# DeMuxRow.net
KiCad netlist of a schematic drawn in EAGLE
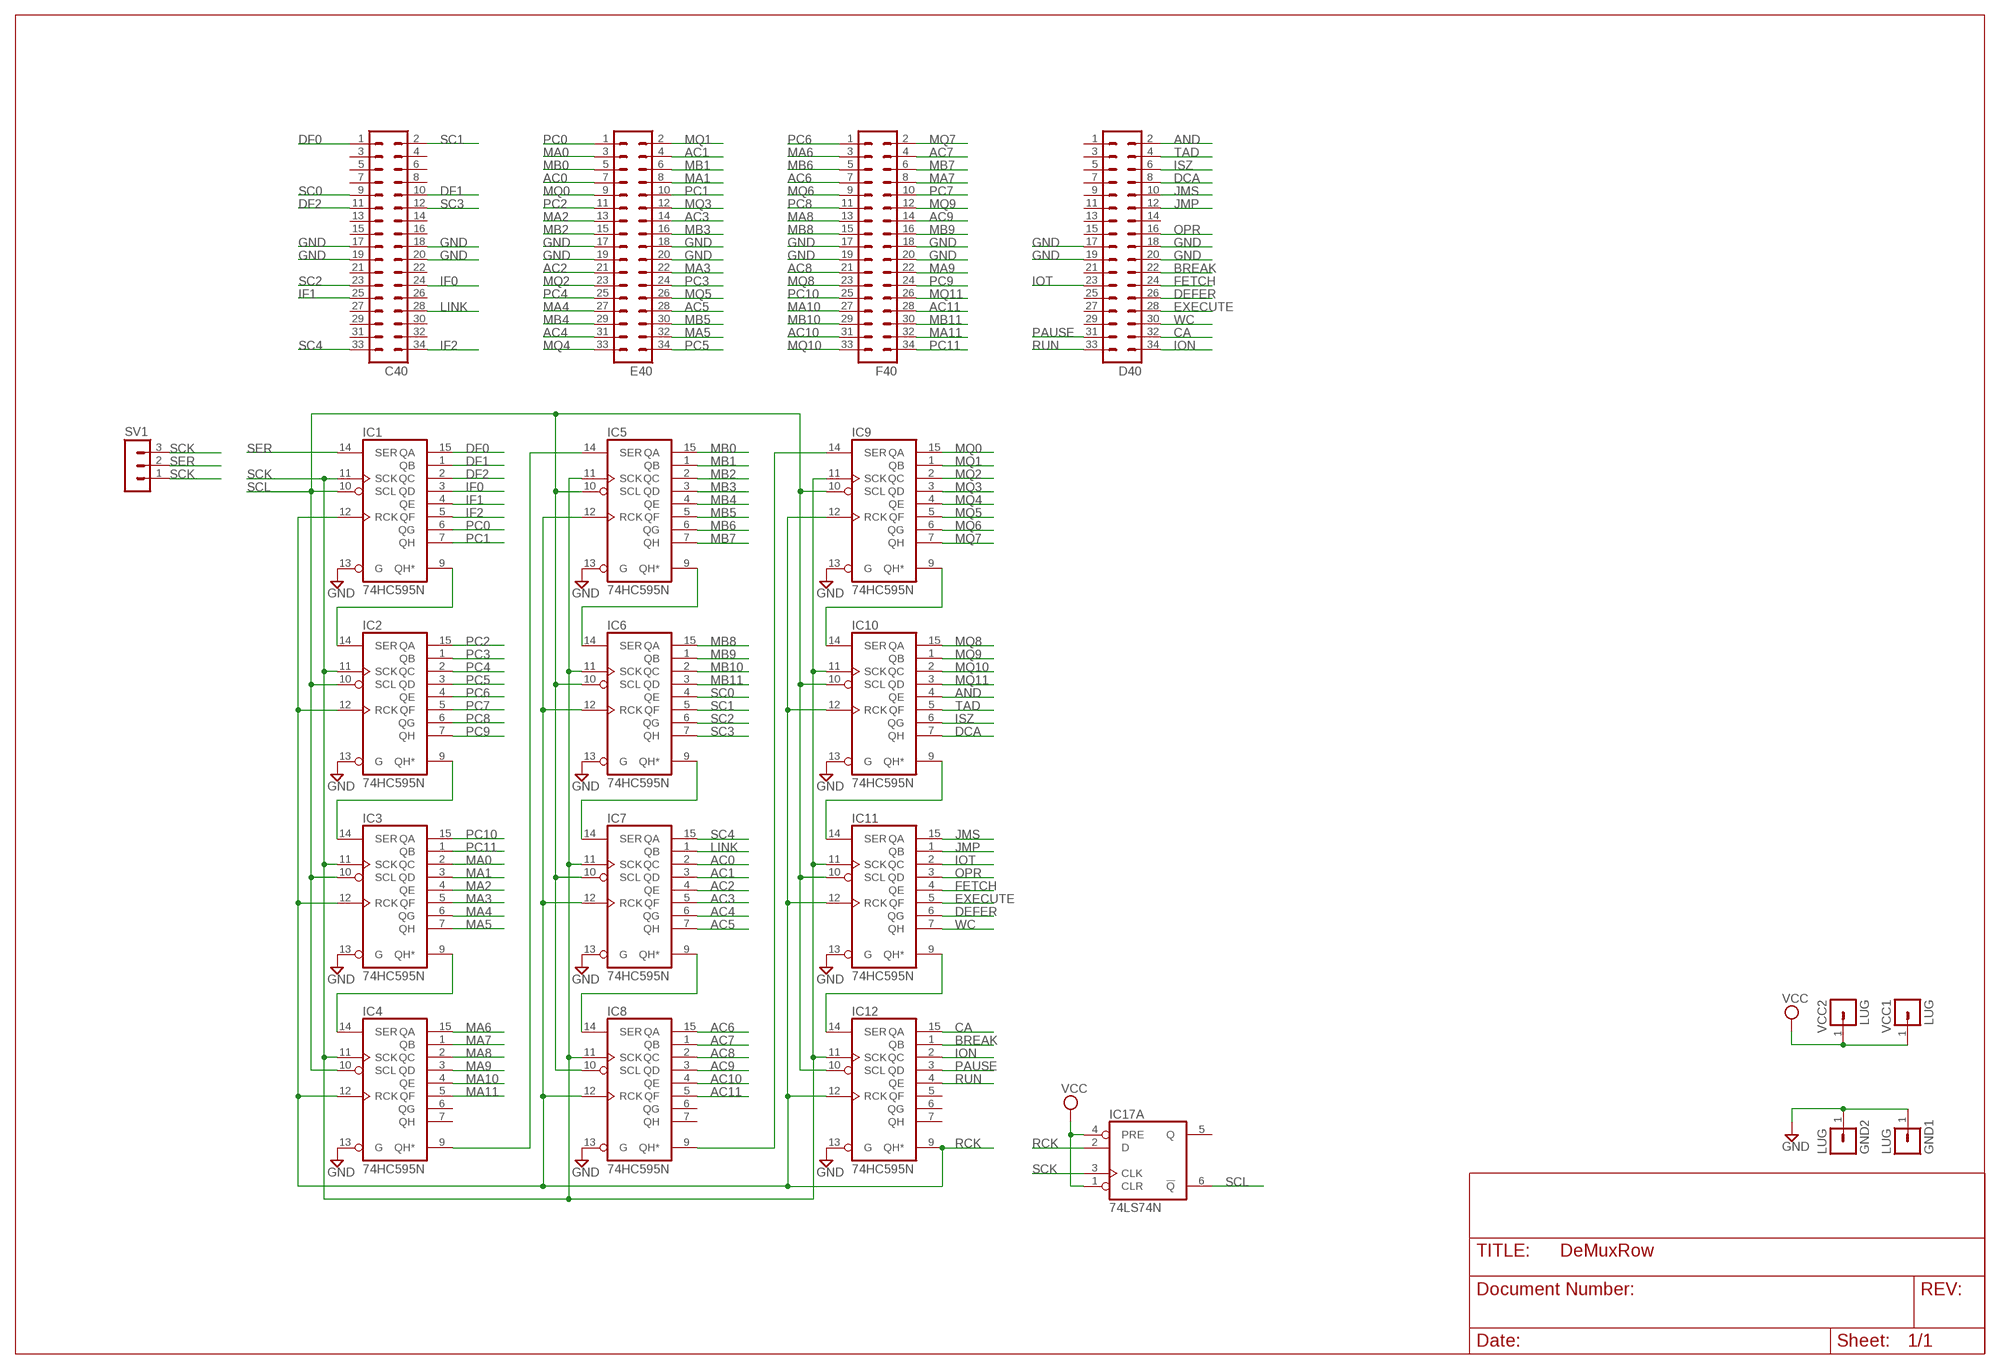
[diagram p0: schematic, sheet 1]

(export (version "E")
  (design (tool "Eeschema 10.0.6"))
  (components
    (comp (ref "C40")
      (value "MA17-2")
      (footprint "eagle-import:MA17-2")
      (libsource (lib "eagle-import") (part "MA17-2"))
    )
    (comp (ref "D40")
      (value "MA17-2")
      (footprint "eagle-import:MA17-2")
      (libsource (lib "eagle-import") (part "MA17-2"))
    )
    (comp (ref "E40")
      (value "MA17-2")
      (footprint "eagle-import:MA17-2")
      (libsource (lib "eagle-import") (part "MA17-2"))
    )
    (comp (ref "F40")
      (value "MA17-2")
      (footprint "eagle-import:MA17-2")
      (libsource (lib "eagle-import") (part "MA17-2"))
    )
    (comp (ref "GND1")
      (value "LUG")
      (footprint "eagle-import:SPADELUG")
      (libsource (lib "eagle-import") (part "LUG"))
    )
    (comp (ref "GND2")
      (value "LUG")
      (footprint "eagle-import:SPADELUG")
      (libsource (lib "eagle-import") (part "LUG"))
    )
    (comp (ref "IC1")
      (value "74HC595N")
      (footprint "eagle-import:DIL16")
      (libsource (lib "eagle-import") (part "74595NLS"))
    )
    (comp (ref "IC2")
      (value "74HC595N")
      (footprint "eagle-import:DIL16")
      (libsource (lib "eagle-import") (part "74595NLS"))
    )
    (comp (ref "IC3")
      (value "74HC595N")
      (footprint "eagle-import:DIL16")
      (libsource (lib "eagle-import") (part "74595NLS"))
    )
    (comp (ref "IC4")
      (value "74HC595N")
      (footprint "eagle-import:DIL16")
      (libsource (lib "eagle-import") (part "74595NLS"))
    )
    (comp (ref "IC5")
      (value "74HC595N")
      (footprint "eagle-import:DIL16")
      (libsource (lib "eagle-import") (part "74595NLS"))
    )
    (comp (ref "IC6")
      (value "74HC595N")
      (footprint "eagle-import:DIL16")
      (libsource (lib "eagle-import") (part "74595NLS"))
    )
    (comp (ref "IC7")
      (value "74HC595N")
      (footprint "eagle-import:DIL16")
      (libsource (lib "eagle-import") (part "74595NLS"))
    )
    (comp (ref "IC8")
      (value "74HC595N")
      (footprint "eagle-import:DIL16")
      (libsource (lib "eagle-import") (part "74595NLS"))
    )
    (comp (ref "IC9")
      (value "74HC595N")
      (footprint "eagle-import:DIL16")
      (libsource (lib "eagle-import") (part "74595NLS"))
    )
    (comp (ref "IC10")
      (value "74HC595N")
      (footprint "eagle-import:DIL16")
      (libsource (lib "eagle-import") (part "74595NLS"))
    )
    (comp (ref "IC11")
      (value "74HC595N")
      (footprint "eagle-import:DIL16")
      (libsource (lib "eagle-import") (part "74595NLS"))
    )
    (comp (ref "IC12")
      (value "74HC595N")
      (footprint "eagle-import:DIL16")
      (libsource (lib "eagle-import") (part "74595NLS"))
    )
    (comp (ref "IC17")
      (value "74LS74N")
      (footprint "eagle-import:DIL14")
      (libsource (lib "eagle-import") (part "7474NLS"))
    )
    (comp (ref "SV1")
      (value "MA03-1")
      (footprint "eagle-import:MA03-1")
      (libsource (lib "eagle-import") (part "MA03-1"))
    )
    (comp (ref "VCC1")
      (value "LUG")
      (footprint "eagle-import:SPADELUG")
      (libsource (lib "eagle-import") (part "LUG"))
    )
    (comp (ref "VCC2")
      (value "LUG")
      (footprint "eagle-import:SPADELUG")
      (libsource (lib "eagle-import") (part "LUG"))
    )
  )
  (nets
    (net (code "1") (name "/AC0") (class "Default")
      (node (ref "E40") (pin "7") (pinfunction "7_7") (pintype "passive"))
      (node (ref "IC7") (pin "2") (pinfunction "QC_2") (pintype "tri_state"))
    )
    (net (code "2") (name "/AC1") (class "Default")
      (node (ref "E40") (pin "4") (pinfunction "4_4") (pintype "passive"))
      (node (ref "IC7") (pin "3") (pinfunction "QD_3") (pintype "tri_state"))
    )
    (net (code "3") (name "/AC2") (class "Default")
      (node (ref "E40") (pin "21") (pinfunction "21_21") (pintype "passive"))
      (node (ref "IC7") (pin "4") (pinfunction "QE_4") (pintype "tri_state"))
    )
    (net (code "4") (name "/AC3") (class "Default")
      (node (ref "E40") (pin "14") (pinfunction "14_14") (pintype "passive"))
      (node (ref "IC7") (pin "5") (pinfunction "QF_5") (pintype "tri_state"))
    )
    (net (code "5") (name "/AC4") (class "Default")
      (node (ref "E40") (pin "31") (pinfunction "31_31") (pintype "passive"))
      (node (ref "IC7") (pin "6") (pinfunction "QG_6") (pintype "tri_state"))
    )
    (net (code "6") (name "/AC5") (class "Default")
      (node (ref "E40") (pin "28") (pinfunction "28_28") (pintype "passive"))
      (node (ref "IC7") (pin "7") (pinfunction "QH_7") (pintype "tri_state"))
    )
    (net (code "7") (name "/AC6") (class "Default")
      (node (ref "F40") (pin "7") (pinfunction "7_7") (pintype "passive"))
      (node (ref "IC8") (pin "15") (pinfunction "QA_15") (pintype "tri_state"))
    )
    (net (code "8") (name "/AC7") (class "Default")
      (node (ref "F40") (pin "4") (pinfunction "4_4") (pintype "passive"))
      (node (ref "IC8") (pin "1") (pinfunction "QB_1") (pintype "tri_state"))
    )
    (net (code "9") (name "/AC8") (class "Default")
      (node (ref "F40") (pin "21") (pinfunction "21_21") (pintype "passive"))
      (node (ref "IC8") (pin "2") (pinfunction "QC_2") (pintype "tri_state"))
    )
    (net (code "10") (name "/AC9") (class "Default")
      (node (ref "F40") (pin "14") (pinfunction "14_14") (pintype "passive"))
      (node (ref "IC8") (pin "3") (pinfunction "QD_3") (pintype "tri_state"))
    )
    (net (code "11") (name "/AC10") (class "Default")
      (node (ref "F40") (pin "31") (pinfunction "31_31") (pintype "passive"))
      (node (ref "IC8") (pin "4") (pinfunction "QE_4") (pintype "tri_state"))
    )
    (net (code "12") (name "/AC11") (class "Default")
      (node (ref "F40") (pin "28") (pinfunction "28_28") (pintype "passive"))
      (node (ref "IC8") (pin "5") (pinfunction "QF_5") (pintype "tri_state"))
    )
    (net (code "13") (name "/AND") (class "Default")
      (node (ref "D40") (pin "2") (pinfunction "2_2") (pintype "passive"))
      (node (ref "IC10") (pin "4") (pinfunction "QE_4") (pintype "tri_state"))
    )
    (net (code "14") (name "/BREAK") (class "Default")
      (node (ref "D40") (pin "22") (pinfunction "22_22") (pintype "passive"))
      (node (ref "IC12") (pin "1") (pinfunction "QB_1") (pintype "tri_state"))
    )
    (net (code "15") (name "/CA") (class "Default")
      (node (ref "D40") (pin "32") (pinfunction "32_32") (pintype "passive"))
      (node (ref "IC12") (pin "15") (pinfunction "QA_15") (pintype "tri_state"))
    )
    (net (code "16") (name "/DCA") (class "Default")
      (node (ref "D40") (pin "8") (pinfunction "8_8") (pintype "passive"))
      (node (ref "IC10") (pin "7") (pinfunction "QH_7") (pintype "tri_state"))
    )
    (net (code "17") (name "/DEFER") (class "Default")
      (node (ref "D40") (pin "26") (pinfunction "26_26") (pintype "passive"))
      (node (ref "IC11") (pin "6") (pinfunction "QG_6") (pintype "tri_state"))
    )
    (net (code "18") (name "/DF0") (class "Default")
      (node (ref "C40") (pin "1") (pinfunction "1_1") (pintype "passive"))
      (node (ref "IC1") (pin "15") (pinfunction "QA_15") (pintype "tri_state"))
    )
    (net (code "19") (name "/DF1") (class "Default")
      (node (ref "C40") (pin "10") (pinfunction "10_10") (pintype "passive"))
      (node (ref "IC1") (pin "1") (pinfunction "QB_1") (pintype "tri_state"))
    )
    (net (code "20") (name "/DF2") (class "Default")
      (node (ref "C40") (pin "11") (pinfunction "11_11") (pintype "passive"))
      (node (ref "IC1") (pin "2") (pinfunction "QC_2") (pintype "tri_state"))
    )
    (net (code "21") (name "/EXECUTE") (class "Default")
      (node (ref "D40") (pin "28") (pinfunction "28_28") (pintype "passive"))
      (node (ref "IC11") (pin "5") (pinfunction "QF_5") (pintype "tri_state"))
    )
    (net (code "22") (name "/FETCH") (class "Default")
      (node (ref "D40") (pin "24") (pinfunction "24_24") (pintype "passive"))
      (node (ref "IC11") (pin "4") (pinfunction "QE_4") (pintype "tri_state"))
    )
    (net (code "23") (name "/IF0") (class "Default")
      (node (ref "C40") (pin "24") (pinfunction "24_24") (pintype "passive"))
      (node (ref "IC1") (pin "3") (pinfunction "QD_3") (pintype "tri_state"))
    )
    (net (code "24") (name "/IF1") (class "Default")
      (node (ref "C40") (pin "25") (pinfunction "25_25") (pintype "passive"))
      (node (ref "IC1") (pin "4") (pinfunction "QE_4") (pintype "tri_state"))
    )
    (net (code "25") (name "/IF2") (class "Default")
      (node (ref "C40") (pin "34") (pinfunction "34_34") (pintype "passive"))
      (node (ref "IC1") (pin "5") (pinfunction "QF_5") (pintype "tri_state"))
    )
    (net (code "26") (name "/ION") (class "Default")
      (node (ref "D40") (pin "34") (pinfunction "34_34") (pintype "passive"))
      (node (ref "IC12") (pin "2") (pinfunction "QC_2") (pintype "tri_state"))
    )
    (net (code "27") (name "/IOT") (class "Default")
      (node (ref "D40") (pin "23") (pinfunction "23_23") (pintype "passive"))
      (node (ref "IC11") (pin "2") (pinfunction "QC_2") (pintype "tri_state"))
    )
    (net (code "28") (name "/ISZ") (class "Default")
      (node (ref "D40") (pin "6") (pinfunction "6_6") (pintype "passive"))
      (node (ref "IC10") (pin "6") (pinfunction "QG_6") (pintype "tri_state"))
    )
    (net (code "29") (name "/JMP") (class "Default")
      (node (ref "D40") (pin "12") (pinfunction "12_12") (pintype "passive"))
      (node (ref "IC11") (pin "1") (pinfunction "QB_1") (pintype "tri_state"))
    )
    (net (code "30") (name "/JMS") (class "Default")
      (node (ref "D40") (pin "10") (pinfunction "10_10") (pintype "passive"))
      (node (ref "IC11") (pin "15") (pinfunction "QA_15") (pintype "tri_state"))
    )
    (net (code "31") (name "/LINK") (class "Default")
      (node (ref "C40") (pin "28") (pinfunction "28_28") (pintype "passive"))
      (node (ref "IC7") (pin "1") (pinfunction "QB_1") (pintype "tri_state"))
    )
    (net (code "32") (name "/MA0") (class "Default")
      (node (ref "E40") (pin "3") (pinfunction "3_3") (pintype "passive"))
      (node (ref "IC3") (pin "2") (pinfunction "QC_2") (pintype "tri_state"))
    )
    (net (code "33") (name "/MA1") (class "Default")
      (node (ref "E40") (pin "8") (pinfunction "8_8") (pintype "passive"))
      (node (ref "IC3") (pin "3") (pinfunction "QD_3") (pintype "tri_state"))
    )
    (net (code "34") (name "/MA2") (class "Default")
      (node (ref "E40") (pin "13") (pinfunction "13_13") (pintype "passive"))
      (node (ref "IC3") (pin "4") (pinfunction "QE_4") (pintype "tri_state"))
    )
    (net (code "35") (name "/MA3") (class "Default")
      (node (ref "E40") (pin "22") (pinfunction "22_22") (pintype "passive"))
      (node (ref "IC3") (pin "5") (pinfunction "QF_5") (pintype "tri_state"))
    )
    (net (code "36") (name "/MA4") (class "Default")
      (node (ref "E40") (pin "27") (pinfunction "27_27") (pintype "passive"))
      (node (ref "IC3") (pin "6") (pinfunction "QG_6") (pintype "tri_state"))
    )
    (net (code "37") (name "/MA5") (class "Default")
      (node (ref "E40") (pin "32") (pinfunction "32_32") (pintype "passive"))
      (node (ref "IC3") (pin "7") (pinfunction "QH_7") (pintype "tri_state"))
    )
    (net (code "38") (name "/MA6") (class "Default")
      (node (ref "F40") (pin "3") (pinfunction "3_3") (pintype "passive"))
      (node (ref "IC4") (pin "15") (pinfunction "QA_15") (pintype "tri_state"))
    )
    (net (code "39") (name "/MA7") (class "Default")
      (node (ref "F40") (pin "8") (pinfunction "8_8") (pintype "passive"))
      (node (ref "IC4") (pin "1") (pinfunction "QB_1") (pintype "tri_state"))
    )
    (net (code "40") (name "/MA8") (class "Default")
      (node (ref "F40") (pin "13") (pinfunction "13_13") (pintype "passive"))
      (node (ref "IC4") (pin "2") (pinfunction "QC_2") (pintype "tri_state"))
    )
    (net (code "41") (name "/MA9") (class "Default")
      (node (ref "F40") (pin "22") (pinfunction "22_22") (pintype "passive"))
      (node (ref "IC4") (pin "3") (pinfunction "QD_3") (pintype "tri_state"))
    )
    (net (code "42") (name "/MA10") (class "Default")
      (node (ref "F40") (pin "27") (pinfunction "27_27") (pintype "passive"))
      (node (ref "IC4") (pin "4") (pinfunction "QE_4") (pintype "tri_state"))
    )
    (net (code "43") (name "/MA11") (class "Default")
      (node (ref "F40") (pin "32") (pinfunction "32_32") (pintype "passive"))
      (node (ref "IC4") (pin "5") (pinfunction "QF_5") (pintype "tri_state"))
    )
    (net (code "44") (name "/MB0") (class "Default")
      (node (ref "E40") (pin "5") (pinfunction "5_5") (pintype "passive"))
      (node (ref "IC5") (pin "15") (pinfunction "QA_15") (pintype "tri_state"))
    )
    (net (code "45") (name "/MB1") (class "Default")
      (node (ref "E40") (pin "6") (pinfunction "6_6") (pintype "passive"))
      (node (ref "IC5") (pin "1") (pinfunction "QB_1") (pintype "tri_state"))
    )
    (net (code "46") (name "/MB2") (class "Default")
      (node (ref "E40") (pin "15") (pinfunction "15_15") (pintype "passive"))
      (node (ref "IC5") (pin "2") (pinfunction "QC_2") (pintype "tri_state"))
    )
    (net (code "47") (name "/MB3") (class "Default")
      (node (ref "E40") (pin "16") (pinfunction "16_16") (pintype "passive"))
      (node (ref "IC5") (pin "3") (pinfunction "QD_3") (pintype "tri_state"))
    )
    (net (code "48") (name "/MB4") (class "Default")
      (node (ref "E40") (pin "29") (pinfunction "29_29") (pintype "passive"))
      (node (ref "IC5") (pin "4") (pinfunction "QE_4") (pintype "tri_state"))
    )
    (net (code "49") (name "/MB5") (class "Default")
      (node (ref "E40") (pin "30") (pinfunction "30_30") (pintype "passive"))
      (node (ref "IC5") (pin "5") (pinfunction "QF_5") (pintype "tri_state"))
    )
    (net (code "50") (name "/MB6") (class "Default")
      (node (ref "F40") (pin "5") (pinfunction "5_5") (pintype "passive"))
      (node (ref "IC5") (pin "6") (pinfunction "QG_6") (pintype "tri_state"))
    )
    (net (code "51") (name "/MB7") (class "Default")
      (node (ref "F40") (pin "6") (pinfunction "6_6") (pintype "passive"))
      (node (ref "IC5") (pin "7") (pinfunction "QH_7") (pintype "tri_state"))
    )
    (net (code "52") (name "/MB8") (class "Default")
      (node (ref "F40") (pin "15") (pinfunction "15_15") (pintype "passive"))
      (node (ref "IC6") (pin "15") (pinfunction "QA_15") (pintype "tri_state"))
    )
    (net (code "53") (name "/MB9") (class "Default")
      (node (ref "F40") (pin "16") (pinfunction "16_16") (pintype "passive"))
      (node (ref "IC6") (pin "1") (pinfunction "QB_1") (pintype "tri_state"))
    )
    (net (code "54") (name "/MB10") (class "Default")
      (node (ref "F40") (pin "29") (pinfunction "29_29") (pintype "passive"))
      (node (ref "IC6") (pin "2") (pinfunction "QC_2") (pintype "tri_state"))
    )
    (net (code "55") (name "/MB11") (class "Default")
      (node (ref "F40") (pin "30") (pinfunction "30_30") (pintype "passive"))
      (node (ref "IC6") (pin "3") (pinfunction "QD_3") (pintype "tri_state"))
    )
    (net (code "56") (name "/MQ0") (class "Default")
      (node (ref "E40") (pin "9") (pinfunction "9_9") (pintype "passive"))
      (node (ref "IC9") (pin "15") (pinfunction "QA_15") (pintype "tri_state"))
    )
    (net (code "57") (name "/MQ1") (class "Default")
      (node (ref "E40") (pin "2") (pinfunction "2_2") (pintype "passive"))
      (node (ref "IC9") (pin "1") (pinfunction "QB_1") (pintype "tri_state"))
    )
    (net (code "58") (name "/MQ2") (class "Default")
      (node (ref "E40") (pin "23") (pinfunction "23_23") (pintype "passive"))
      (node (ref "IC9") (pin "2") (pinfunction "QC_2") (pintype "tri_state"))
    )
    (net (code "59") (name "/MQ3") (class "Default")
      (node (ref "E40") (pin "12") (pinfunction "12_12") (pintype "passive"))
      (node (ref "IC9") (pin "3") (pinfunction "QD_3") (pintype "tri_state"))
    )
    (net (code "60") (name "/MQ4") (class "Default")
      (node (ref "E40") (pin "33") (pinfunction "33_33") (pintype "passive"))
      (node (ref "IC9") (pin "4") (pinfunction "QE_4") (pintype "tri_state"))
    )
    (net (code "61") (name "/MQ5") (class "Default")
      (node (ref "E40") (pin "26") (pinfunction "26_26") (pintype "passive"))
      (node (ref "IC9") (pin "5") (pinfunction "QF_5") (pintype "tri_state"))
    )
    (net (code "62") (name "/MQ6") (class "Default")
      (node (ref "F40") (pin "9") (pinfunction "9_9") (pintype "passive"))
      (node (ref "IC9") (pin "6") (pinfunction "QG_6") (pintype "tri_state"))
    )
    (net (code "63") (name "/MQ7") (class "Default")
      (node (ref "F40") (pin "2") (pinfunction "2_2") (pintype "passive"))
      (node (ref "IC9") (pin "7") (pinfunction "QH_7") (pintype "tri_state"))
    )
    (net (code "64") (name "/MQ8") (class "Default")
      (node (ref "F40") (pin "23") (pinfunction "23_23") (pintype "passive"))
      (node (ref "IC10") (pin "15") (pinfunction "QA_15") (pintype "tri_state"))
    )
    (net (code "65") (name "/MQ9") (class "Default")
      (node (ref "F40") (pin "12") (pinfunction "12_12") (pintype "passive"))
      (node (ref "IC10") (pin "1") (pinfunction "QB_1") (pintype "tri_state"))
    )
    (net (code "66") (name "/MQ10") (class "Default")
      (node (ref "F40") (pin "33") (pinfunction "33_33") (pintype "passive"))
      (node (ref "IC10") (pin "2") (pinfunction "QC_2") (pintype "tri_state"))
    )
    (net (code "67") (name "/MQ11") (class "Default")
      (node (ref "F40") (pin "26") (pinfunction "26_26") (pintype "passive"))
      (node (ref "IC10") (pin "3") (pinfunction "QD_3") (pintype "tri_state"))
    )
    (net (code "68") (name "/OPR") (class "Default")
      (node (ref "D40") (pin "16") (pinfunction "16_16") (pintype "passive"))
      (node (ref "IC11") (pin "3") (pinfunction "QD_3") (pintype "tri_state"))
    )
    (net (code "69") (name "/PAUSE") (class "Default")
      (node (ref "D40") (pin "31") (pinfunction "31_31") (pintype "passive"))
      (node (ref "IC12") (pin "3") (pinfunction "QD_3") (pintype "tri_state"))
    )
    (net (code "70") (name "/PC0") (class "Default")
      (node (ref "E40") (pin "1") (pinfunction "1_1") (pintype "passive"))
      (node (ref "IC1") (pin "6") (pinfunction "QG_6") (pintype "tri_state"))
    )
    (net (code "71") (name "/PC1") (class "Default")
      (node (ref "E40") (pin "10") (pinfunction "10_10") (pintype "passive"))
      (node (ref "IC1") (pin "7") (pinfunction "QH_7") (pintype "tri_state"))
    )
    (net (code "72") (name "/PC2") (class "Default")
      (node (ref "E40") (pin "11") (pinfunction "11_11") (pintype "passive"))
      (node (ref "IC2") (pin "15") (pinfunction "QA_15") (pintype "tri_state"))
    )
    (net (code "73") (name "/PC3") (class "Default")
      (node (ref "E40") (pin "24") (pinfunction "24_24") (pintype "passive"))
      (node (ref "IC2") (pin "1") (pinfunction "QB_1") (pintype "tri_state"))
    )
    (net (code "74") (name "/PC4") (class "Default")
      (node (ref "E40") (pin "25") (pinfunction "25_25") (pintype "passive"))
      (node (ref "IC2") (pin "2") (pinfunction "QC_2") (pintype "tri_state"))
    )
    (net (code "75") (name "/PC5") (class "Default")
      (node (ref "E40") (pin "34") (pinfunction "34_34") (pintype "passive"))
      (node (ref "IC2") (pin "3") (pinfunction "QD_3") (pintype "tri_state"))
    )
    (net (code "76") (name "/PC6") (class "Default")
      (node (ref "F40") (pin "1") (pinfunction "1_1") (pintype "passive"))
      (node (ref "IC2") (pin "4") (pinfunction "QE_4") (pintype "tri_state"))
    )
    (net (code "77") (name "/PC7") (class "Default")
      (node (ref "F40") (pin "10") (pinfunction "10_10") (pintype "passive"))
      (node (ref "IC2") (pin "5") (pinfunction "QF_5") (pintype "tri_state"))
    )
    (net (code "78") (name "/PC8") (class "Default")
      (node (ref "F40") (pin "11") (pinfunction "11_11") (pintype "passive"))
      (node (ref "IC2") (pin "6") (pinfunction "QG_6") (pintype "tri_state"))
    )
    (net (code "79") (name "/PC9") (class "Default")
      (node (ref "F40") (pin "24") (pinfunction "24_24") (pintype "passive"))
      (node (ref "IC2") (pin "7") (pinfunction "QH_7") (pintype "tri_state"))
    )
    (net (code "80") (name "/PC10") (class "Default")
      (node (ref "F40") (pin "25") (pinfunction "25_25") (pintype "passive"))
      (node (ref "IC3") (pin "15") (pinfunction "QA_15") (pintype "tri_state"))
    )
    (net (code "81") (name "/PC11") (class "Default")
      (node (ref "F40") (pin "34") (pinfunction "34_34") (pintype "passive"))
      (node (ref "IC3") (pin "1") (pinfunction "QB_1") (pintype "tri_state"))
    )
    (net (code "82") (name "/RCK") (class "Default")
      (node (ref "IC1") (pin "12") (pinfunction "RCK_12") (pintype "input"))
      (node (ref "IC10") (pin "12") (pinfunction "RCK_12") (pintype "input"))
      (node (ref "IC11") (pin "12") (pinfunction "RCK_12") (pintype "input"))
      (node (ref "IC12") (pin "12") (pinfunction "RCK_12") (pintype "input"))
      (node (ref "IC12") (pin "9") (pinfunction "QH*_9") (pintype "tri_state"))
      (node (ref "IC17") (pin "2") (pinfunction "D_2") (pintype "input"))
      (node (ref "IC2") (pin "12") (pinfunction "RCK_12") (pintype "input"))
      (node (ref "IC3") (pin "12") (pinfunction "RCK_12") (pintype "input"))
      (node (ref "IC4") (pin "12") (pinfunction "RCK_12") (pintype "input"))
      (node (ref "IC5") (pin "12") (pinfunction "RCK_12") (pintype "input"))
      (node (ref "IC6") (pin "12") (pinfunction "RCK_12") (pintype "input"))
      (node (ref "IC7") (pin "12") (pinfunction "RCK_12") (pintype "input"))
      (node (ref "IC8") (pin "12") (pinfunction "RCK_12") (pintype "input"))
      (node (ref "IC9") (pin "12") (pinfunction "RCK_12") (pintype "input"))
    )
    (net (code "83") (name "/RUN") (class "Default")
      (node (ref "D40") (pin "33") (pinfunction "33_33") (pintype "passive"))
      (node (ref "IC12") (pin "4") (pinfunction "QE_4") (pintype "tri_state"))
    )
    (net (code "84") (name "/SC0") (class "Default")
      (node (ref "C40") (pin "9") (pinfunction "9_9") (pintype "passive"))
      (node (ref "IC6") (pin "4") (pinfunction "QE_4") (pintype "tri_state"))
    )
    (net (code "85") (name "/SC1") (class "Default")
      (node (ref "C40") (pin "2") (pinfunction "2_2") (pintype "passive"))
      (node (ref "IC6") (pin "5") (pinfunction "QF_5") (pintype "tri_state"))
    )
    (net (code "86") (name "/SC2") (class "Default")
      (node (ref "C40") (pin "23") (pinfunction "23_23") (pintype "passive"))
      (node (ref "IC6") (pin "6") (pinfunction "QG_6") (pintype "tri_state"))
    )
    (net (code "87") (name "/SC3") (class "Default")
      (node (ref "C40") (pin "12") (pinfunction "12_12") (pintype "passive"))
      (node (ref "IC6") (pin "7") (pinfunction "QH_7") (pintype "tri_state"))
    )
    (net (code "88") (name "/SC4") (class "Default")
      (node (ref "C40") (pin "33") (pinfunction "33_33") (pintype "passive"))
      (node (ref "IC7") (pin "15") (pinfunction "QA_15") (pintype "tri_state"))
    )
    (net (code "89") (name "/SCK") (class "Default")
      (node (ref "IC1") (pin "11") (pinfunction "SCK_11") (pintype "input"))
      (node (ref "IC10") (pin "11") (pinfunction "SCK_11") (pintype "input"))
      (node (ref "IC11") (pin "11") (pinfunction "SCK_11") (pintype "input"))
      (node (ref "IC12") (pin "11") (pinfunction "SCK_11") (pintype "input"))
      (node (ref "IC17") (pin "3") (pinfunction "CLK_3") (pintype "input"))
      (node (ref "IC2") (pin "11") (pinfunction "SCK_11") (pintype "input"))
      (node (ref "IC3") (pin "11") (pinfunction "SCK_11") (pintype "input"))
      (node (ref "IC4") (pin "11") (pinfunction "SCK_11") (pintype "input"))
      (node (ref "IC5") (pin "11") (pinfunction "SCK_11") (pintype "input"))
      (node (ref "IC6") (pin "11") (pinfunction "SCK_11") (pintype "input"))
      (node (ref "IC7") (pin "11") (pinfunction "SCK_11") (pintype "input"))
      (node (ref "IC8") (pin "11") (pinfunction "SCK_11") (pintype "input"))
      (node (ref "IC9") (pin "11") (pinfunction "SCK_11") (pintype "input"))
      (node (ref "SV1") (pin "1") (pinfunction "1_1") (pintype "passive"))
      (node (ref "SV1") (pin "3") (pinfunction "3_3") (pintype "passive"))
    )
    (net (code "90") (name "/SCL") (class "Default")
      (node (ref "IC1") (pin "10") (pinfunction "SCL_10") (pintype "input"))
      (node (ref "IC10") (pin "10") (pinfunction "SCL_10") (pintype "input"))
      (node (ref "IC11") (pin "10") (pinfunction "SCL_10") (pintype "input"))
      (node (ref "IC12") (pin "10") (pinfunction "SCL_10") (pintype "input"))
      (node (ref "IC17") (pin "6") (pinfunction "~{Q}_6") (pintype "output"))
      (node (ref "IC2") (pin "10") (pinfunction "SCL_10") (pintype "input"))
      (node (ref "IC3") (pin "10") (pinfunction "SCL_10") (pintype "input"))
      (node (ref "IC4") (pin "10") (pinfunction "SCL_10") (pintype "input"))
      (node (ref "IC5") (pin "10") (pinfunction "SCL_10") (pintype "input"))
      (node (ref "IC6") (pin "10") (pinfunction "SCL_10") (pintype "input"))
      (node (ref "IC7") (pin "10") (pinfunction "SCL_10") (pintype "input"))
      (node (ref "IC8") (pin "10") (pinfunction "SCL_10") (pintype "input"))
      (node (ref "IC9") (pin "10") (pinfunction "SCL_10") (pintype "input"))
    )
    (net (code "91") (name "/SER") (class "Default")
      (node (ref "IC1") (pin "14") (pinfunction "SER_14") (pintype "input"))
      (node (ref "SV1") (pin "2") (pinfunction "2_2") (pintype "passive"))
    )
    (net (code "92") (name "/TAD") (class "Default")
      (node (ref "D40") (pin "4") (pinfunction "4_4") (pintype "passive"))
      (node (ref "IC10") (pin "5") (pinfunction "QF_5") (pintype "tri_state"))
    )
    (net (code "93") (name "/WC") (class "Default")
      (node (ref "D40") (pin "30") (pinfunction "30_30") (pintype "passive"))
      (node (ref "IC11") (pin "7") (pinfunction "QH_7") (pintype "tri_state"))
    )
    (net (code "94") (name "GND") (class "Default")
      (node (ref "C40") (pin "17") (pinfunction "17_17") (pintype "passive"))
      (node (ref "C40") (pin "18") (pinfunction "18_18") (pintype "passive"))
      (node (ref "C40") (pin "19") (pinfunction "19_19") (pintype "passive"))
      (node (ref "C40") (pin "20") (pinfunction "20_20") (pintype "passive"))
      (node (ref "D40") (pin "17") (pinfunction "17_17") (pintype "passive"))
      (node (ref "D40") (pin "18") (pinfunction "18_18") (pintype "passive"))
      (node (ref "D40") (pin "19") (pinfunction "19_19") (pintype "passive"))
      (node (ref "D40") (pin "20") (pinfunction "20_20") (pintype "passive"))
      (node (ref "E40") (pin "17") (pinfunction "17_17") (pintype "passive"))
      (node (ref "E40") (pin "18") (pinfunction "18_18") (pintype "passive"))
      (node (ref "E40") (pin "19") (pinfunction "19_19") (pintype "passive"))
      (node (ref "E40") (pin "20") (pinfunction "20_20") (pintype "passive"))
      (node (ref "F40") (pin "17") (pinfunction "17_17") (pintype "passive"))
      (node (ref "F40") (pin "18") (pinfunction "18_18") (pintype "passive"))
      (node (ref "F40") (pin "19") (pinfunction "19_19") (pintype "passive"))
      (node (ref "F40") (pin "20") (pinfunction "20_20") (pintype "passive"))
      (node (ref "GND1") (pin "1") (pinfunction "1_1") (pintype "passive"))
      (node (ref "GND2") (pin "1") (pinfunction "1_1") (pintype "passive"))
      (node (ref "IC1") (pin "13") (pinfunction "G_13") (pintype "input"))
      (node (ref "IC10") (pin "13") (pinfunction "G_13") (pintype "input"))
      (node (ref "IC11") (pin "13") (pinfunction "G_13") (pintype "input"))
      (node (ref "IC12") (pin "13") (pinfunction "G_13") (pintype "input"))
      (node (ref "IC2") (pin "13") (pinfunction "G_13") (pintype "input"))
      (node (ref "IC3") (pin "13") (pinfunction "G_13") (pintype "input"))
      (node (ref "IC4") (pin "13") (pinfunction "G_13") (pintype "input"))
      (node (ref "IC5") (pin "13") (pinfunction "G_13") (pintype "input"))
      (node (ref "IC6") (pin "13") (pinfunction "G_13") (pintype "input"))
      (node (ref "IC7") (pin "13") (pinfunction "G_13") (pintype "input"))
      (node (ref "IC8") (pin "13") (pinfunction "G_13") (pintype "input"))
      (node (ref "IC9") (pin "13") (pinfunction "G_13") (pintype "input"))
    )
    (net (code "95") (name "Net-(IC1A-QH*)") (class "Default")
      (node (ref "IC1") (pin "9") (pinfunction "QH*_9") (pintype "tri_state"))
      (node (ref "IC2") (pin "14") (pinfunction "SER_14") (pintype "input"))
    )
    (net (code "96") (name "Net-(IC2A-QH*)") (class "Default")
      (node (ref "IC2") (pin "9") (pinfunction "QH*_9") (pintype "tri_state"))
      (node (ref "IC3") (pin "14") (pinfunction "SER_14") (pintype "input"))
    )
    (net (code "97") (name "Net-(IC3A-QH*)") (class "Default")
      (node (ref "IC3") (pin "9") (pinfunction "QH*_9") (pintype "tri_state"))
      (node (ref "IC4") (pin "14") (pinfunction "SER_14") (pintype "input"))
    )
    (net (code "98") (name "Net-(IC4A-QH*)") (class "Default")
      (node (ref "IC4") (pin "9") (pinfunction "QH*_9") (pintype "tri_state"))
      (node (ref "IC5") (pin "14") (pinfunction "SER_14") (pintype "input"))
    )
    (net (code "99") (name "Net-(IC5A-QH*)") (class "Default")
      (node (ref "IC5") (pin "9") (pinfunction "QH*_9") (pintype "tri_state"))
      (node (ref "IC6") (pin "14") (pinfunction "SER_14") (pintype "input"))
    )
    (net (code "100") (name "Net-(IC6A-QH*)") (class "Default")
      (node (ref "IC6") (pin "9") (pinfunction "QH*_9") (pintype "tri_state"))
      (node (ref "IC7") (pin "14") (pinfunction "SER_14") (pintype "input"))
    )
    (net (code "101") (name "Net-(IC7A-QH*)") (class "Default")
      (node (ref "IC7") (pin "9") (pinfunction "QH*_9") (pintype "tri_state"))
      (node (ref "IC8") (pin "14") (pinfunction "SER_14") (pintype "input"))
    )
    (net (code "102") (name "Net-(IC8A-QH*)") (class "Default")
      (node (ref "IC8") (pin "9") (pinfunction "QH*_9") (pintype "tri_state"))
      (node (ref "IC9") (pin "14") (pinfunction "SER_14") (pintype "input"))
    )
    (net (code "103") (name "Net-(IC10A-QH*)") (class "Default")
      (node (ref "IC10") (pin "9") (pinfunction "QH*_9") (pintype "tri_state"))
      (node (ref "IC11") (pin "14") (pinfunction "SER_14") (pintype "input"))
    )
    (net (code "104") (name "Net-(IC10A-SER)") (class "Default")
      (node (ref "IC10") (pin "14") (pinfunction "SER_14") (pintype "input"))
      (node (ref "IC9") (pin "9") (pinfunction "QH*_9") (pintype "tri_state"))
    )
    (net (code "105") (name "Net-(IC11A-QH*)") (class "Default")
      (node (ref "IC11") (pin "9") (pinfunction "QH*_9") (pintype "tri_state"))
      (node (ref "IC12") (pin "14") (pinfunction "SER_14") (pintype "input"))
    )
    (net (code "106") (name "VCC") (class "Default")
      (node (ref "IC17") (pin "1") (pinfunction "CLR_1") (pintype "input"))
      (node (ref "IC17") (pin "4") (pinfunction "PRE_4") (pintype "input"))
      (node (ref "VCC1") (pin "1") (pinfunction "1_1") (pintype "passive"))
      (node (ref "VCC2") (pin "1") (pinfunction "1_1") (pintype "passive"))
    )
    (net (code "107") (name "unconnected-(C40-Pad3)") (class "Default")
      (node (ref "C40") (pin "3") (pinfunction "3_3") (pintype "passive"))
    )
    (net (code "108") (name "unconnected-(C40-Pad4)") (class "Default")
      (node (ref "C40") (pin "4") (pinfunction "4_4") (pintype "passive"))
    )
    (net (code "109") (name "unconnected-(C40-Pad5)") (class "Default")
      (node (ref "C40") (pin "5") (pinfunction "5_5") (pintype "passive"))
    )
    (net (code "110") (name "unconnected-(C40-Pad6)") (class "Default")
      (node (ref "C40") (pin "6") (pinfunction "6_6") (pintype "passive"))
    )
    (net (code "111") (name "unconnected-(C40-Pad7)") (class "Default")
      (node (ref "C40") (pin "7") (pinfunction "7_7") (pintype "passive"))
    )
    (net (code "112") (name "unconnected-(C40-Pad8)") (class "Default")
      (node (ref "C40") (pin "8") (pinfunction "8_8") (pintype "passive"))
    )
    (net (code "113") (name "unconnected-(C40-Pad13)") (class "Default")
      (node (ref "C40") (pin "13") (pinfunction "13_13") (pintype "passive"))
    )
    (net (code "114") (name "unconnected-(C40-Pad14)") (class "Default")
      (node (ref "C40") (pin "14") (pinfunction "14_14") (pintype "passive"))
    )
    (net (code "115") (name "unconnected-(C40-Pad15)") (class "Default")
      (node (ref "C40") (pin "15") (pinfunction "15_15") (pintype "passive"))
    )
    (net (code "116") (name "unconnected-(C40-Pad16)") (class "Default")
      (node (ref "C40") (pin "16") (pinfunction "16_16") (pintype "passive"))
    )
    (net (code "117") (name "unconnected-(C40-Pad21)") (class "Default")
      (node (ref "C40") (pin "21") (pinfunction "21_21") (pintype "passive"))
    )
    (net (code "118") (name "unconnected-(C40-Pad22)") (class "Default")
      (node (ref "C40") (pin "22") (pinfunction "22_22") (pintype "passive"))
    )
    (net (code "119") (name "unconnected-(C40-Pad26)") (class "Default")
      (node (ref "C40") (pin "26") (pinfunction "26_26") (pintype "passive"))
    )
    (net (code "120") (name "unconnected-(C40-Pad27)") (class "Default")
      (node (ref "C40") (pin "27") (pinfunction "27_27") (pintype "passive"))
    )
    (net (code "121") (name "unconnected-(C40-Pad29)") (class "Default")
      (node (ref "C40") (pin "29") (pinfunction "29_29") (pintype "passive"))
    )
    (net (code "122") (name "unconnected-(C40-Pad30)") (class "Default")
      (node (ref "C40") (pin "30") (pinfunction "30_30") (pintype "passive"))
    )
    (net (code "123") (name "unconnected-(C40-Pad31)") (class "Default")
      (node (ref "C40") (pin "31") (pinfunction "31_31") (pintype "passive"))
    )
    (net (code "124") (name "unconnected-(C40-Pad32)") (class "Default")
      (node (ref "C40") (pin "32") (pinfunction "32_32") (pintype "passive"))
    )
    (net (code "125") (name "unconnected-(D40-Pad1)") (class "Default")
      (node (ref "D40") (pin "1") (pinfunction "1_1") (pintype "passive"))
    )
    (net (code "126") (name "unconnected-(D40-Pad3)") (class "Default")
      (node (ref "D40") (pin "3") (pinfunction "3_3") (pintype "passive"))
    )
    (net (code "127") (name "unconnected-(D40-Pad5)") (class "Default")
      (node (ref "D40") (pin "5") (pinfunction "5_5") (pintype "passive"))
    )
    (net (code "128") (name "unconnected-(D40-Pad7)") (class "Default")
      (node (ref "D40") (pin "7") (pinfunction "7_7") (pintype "passive"))
    )
    (net (code "129") (name "unconnected-(D40-Pad9)") (class "Default")
      (node (ref "D40") (pin "9") (pinfunction "9_9") (pintype "passive"))
    )
    (net (code "130") (name "unconnected-(D40-Pad11)") (class "Default")
      (node (ref "D40") (pin "11") (pinfunction "11_11") (pintype "passive"))
    )
    (net (code "131") (name "unconnected-(D40-Pad13)") (class "Default")
      (node (ref "D40") (pin "13") (pinfunction "13_13") (pintype "passive"))
    )
    (net (code "132") (name "unconnected-(D40-Pad14)") (class "Default")
      (node (ref "D40") (pin "14") (pinfunction "14_14") (pintype "passive"))
    )
    (net (code "133") (name "unconnected-(D40-Pad15)") (class "Default")
      (node (ref "D40") (pin "15") (pinfunction "15_15") (pintype "passive"))
    )
    (net (code "134") (name "unconnected-(D40-Pad21)") (class "Default")
      (node (ref "D40") (pin "21") (pinfunction "21_21") (pintype "passive"))
    )
    (net (code "135") (name "unconnected-(D40-Pad25)") (class "Default")
      (node (ref "D40") (pin "25") (pinfunction "25_25") (pintype "passive"))
    )
    (net (code "136") (name "unconnected-(D40-Pad27)") (class "Default")
      (node (ref "D40") (pin "27") (pinfunction "27_27") (pintype "passive"))
    )
    (net (code "137") (name "unconnected-(D40-Pad29)") (class "Default")
      (node (ref "D40") (pin "29") (pinfunction "29_29") (pintype "passive"))
    )
    (net (code "138") (name "unconnected-(IC4A-QG-Pad6)") (class "Default")
      (node (ref "IC4") (pin "6") (pinfunction "QG_6") (pintype "tri_state"))
    )
    (net (code "139") (name "unconnected-(IC4A-QH-Pad7)") (class "Default")
      (node (ref "IC4") (pin "7") (pinfunction "QH_7") (pintype "tri_state"))
    )
    (net (code "140") (name "unconnected-(IC8A-QG-Pad6)") (class "Default")
      (node (ref "IC8") (pin "6") (pinfunction "QG_6") (pintype "tri_state"))
    )
    (net (code "141") (name "unconnected-(IC8A-QH-Pad7)") (class "Default")
      (node (ref "IC8") (pin "7") (pinfunction "QH_7") (pintype "tri_state"))
    )
    (net (code "142") (name "unconnected-(IC12A-QF-Pad5)") (class "Default")
      (node (ref "IC12") (pin "5") (pinfunction "QF_5") (pintype "tri_state"))
    )
    (net (code "143") (name "unconnected-(IC12A-QG-Pad6)") (class "Default")
      (node (ref "IC12") (pin "6") (pinfunction "QG_6") (pintype "tri_state"))
    )
    (net (code "144") (name "unconnected-(IC12A-QH-Pad7)") (class "Default")
      (node (ref "IC12") (pin "7") (pinfunction "QH_7") (pintype "tri_state"))
    )
    (net (code "145") (name "unconnected-(IC17A-Q-Pad5)") (class "Default")
      (node (ref "IC17") (pin "5") (pinfunction "Q_5") (pintype "output"))
    )
  )
)
